# SoC_Supply.net
KiCad netlist of a schematic drawn in Altium Designer
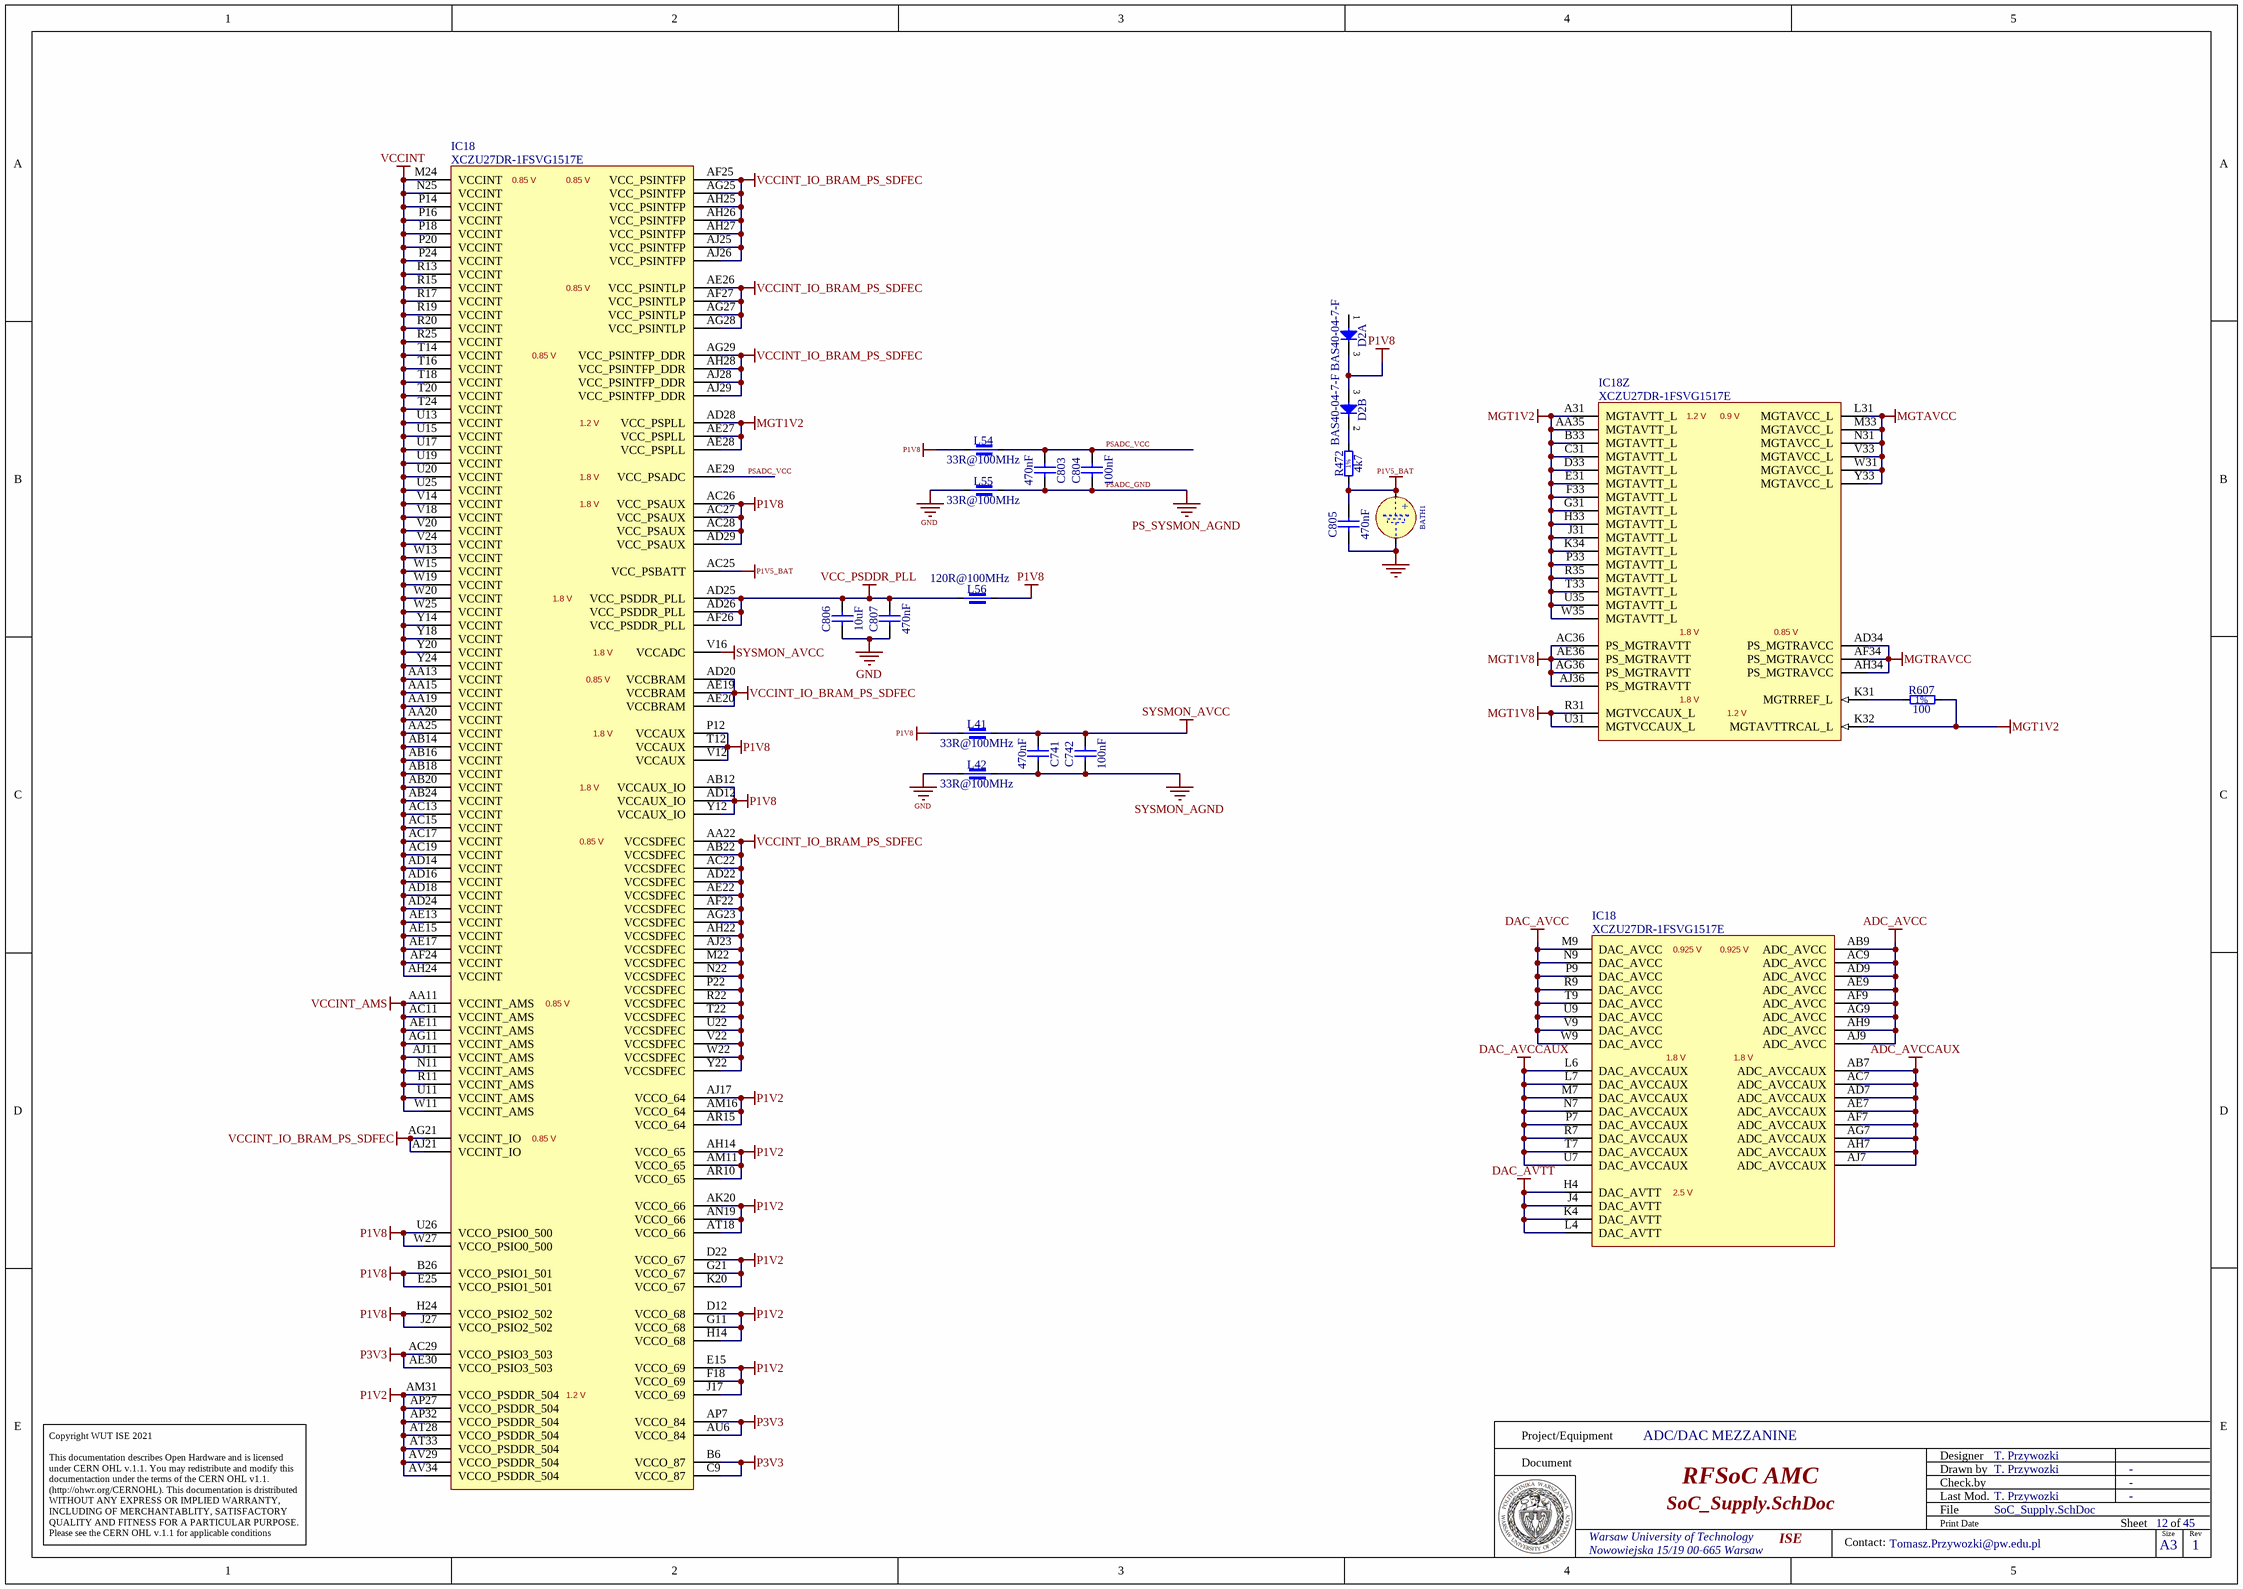
[diagram p0: SoC_Supply.SchDoc]

(export (version "E")
  (design (tool "Eeschema 10.0.6"))
  (components
    (comp (ref "BATH1")
      (value "~")
      (footprint "BATH_KEYSTONE_2998")
      (description "Battery Holder whit 2 Pin")
      (fields
        (field (name "PART NUMBER") "BATH_KEYSTONE_2998")
        (field (name "MANUFACTURER") "KEYSTONE")
        (field (name "AUTHOR") "CERN DEM JLC")
      )
      (libsource (lib "Eletro-mechanical") (part "Battery Holder 2 Pin"))
    )
    (comp (ref "C741")
      (value "470nF")
      (footprint "CAPC0603X33N")
      (description "Non-polarised capacitor")
      (fields
        (field (name "MANUFACTURER PART NUMBER") "CC0201_470NF_4V_20%_X5R")
        (field (name "MANUFACTURER") "GENERIC")
        (field (name "AUTHOR") "CERN DEM JLC")
      )
      (libsource (lib "Capacitors") (part "Capacitor - non polarized"))
    )
    (comp (ref "C742")
      (value "100nF")
      (footprint "CAPC1005X55N")
      (description "Non-polarised capacitor")
      (fields
        (field (name "PART NUMBER") "CC0402_100NF_25V_10%_X7R_YUDEN_TMK105B7104KVHF")
        (field (name "VOLTAGE") "25V")
        (field (name "AUTHOR") "CERN DEM JLC")
      )
      (libsource (lib "Capacitors") (part "Capacitor - non polarized"))
    )
    (comp (ref "C803")
      (value "470nF")
      (footprint "CAPC0603X33N")
      (description "Non-polarised capacitor")
      (fields
        (field (name "MANUFACTURER PART NUMBER") "CC0201_470NF_4V_20%_X5R")
        (field (name "MANUFACTURER") "GENERIC")
        (field (name "AUTHOR") "CERN DEM JLC")
      )
      (libsource (lib "Capacitors") (part "Capacitor - non polarized"))
    )
    (comp (ref "C804")
      (value "100nF")
      (footprint "CAPC1005X55N")
      (description "Non-polarised capacitor")
      (fields
        (field (name "PART NUMBER") "CC0402_100NF_25V_10%_X7R_YUDEN_TMK105B7104KVHF")
        (field (name "VOLTAGE") "25V")
        (field (name "AUTHOR") "CERN DEM JLC")
      )
      (libsource (lib "Capacitors") (part "Capacitor - non polarized"))
    )
    (comp (ref "C805")
      (value "470nF")
      (footprint "CAPC0603X33N")
      (description "Non-polarised capacitor")
      (fields
        (field (name "MANUFACTURER PART NUMBER") "CC0201_470NF_4V_20%_X5R")
        (field (name "MANUFACTURER") "GENERIC")
        (field (name "AUTHOR") "CERN DEM JLC")
      )
      (libsource (lib "Capacitors") (part "Capacitor - non polarized"))
    )
    (comp (ref "C806")
      (value "10uF")
      (footprint "CAPC1608X80N")
      (description "Non-polarised capacitor")
      (fields
        (field (name "PART NUMBER") "CC0603_10UF_10V_10%_X5R")
        (field (name "VOLTAGE") "10V")
        (field (name "AUTHOR") "CERN DEM JLC")
      )
      (libsource (lib "Capacitors") (part "Capacitor - non polarized"))
    )
    (comp (ref "C807")
      (value "470nF")
      (footprint "CAPC1005X55N")
      (description "Non-polarised capacitor")
      (fields
        (field (name "PART NUMBER") "CC0402_470NF_16V_10%_X5R")
        (field (name "VOLTAGE") "16V")
        (field (name "AUTHOR") "CERN DEM JLC")
      )
      (libsource (lib "Capacitors") (part "Capacitor - non polarized"))
    )
    (comp (ref "D2")
      (value "BAS40-04-7-F")
      (footprint "SOT95P240X110-3N")
      (description "Serial Diode")
      (fields
        (field (name "VOLTAGE") "40V")
        (field (name "POWER") "200mA")
        (field (name "AUTHOR") "CERN DEM JLC")
      )
      (libsource (lib "ICs And Semiconductors") (part "Diode x2 A1C3_A3C2"))
    )
    (comp (ref "IC18")
      (value "XCZU27DR-1FSVG1517E")
      (footprint "XILINX_FSVG1517 (XCZU27DR)")
      (fields (field (name "MANUFACTURER") "XILINX") (field (name "AUTHOR") "CERN DEM MR"))
      (libsource (lib "ICs And Semiconductors") (part "XCZU27DR-1FSVG1517E"))
    )
    (comp (ref "L41")
      (value "33R@100MHz")
      (footprint "INDC1005X55N")
      (fields
        (field (name "MANUFACTURER PART NUMBER") "BLM15PX330SN1D")
        (field (name "MANUFACTURER") "MURATA")
        (field (name "PART NUMBER") "IND0402_MURATA_BLM15PX330SN1D")
        (field (name "AUTHOR") "CERN DEM JMW")
      )
      (libsource (lib "Inductors & Transformers") (part "Ferrite Bead"))
    )
    (comp (ref "L42")
      (value "33R@100MHz")
      (footprint "INDC1005X55N")
      (fields
        (field (name "MANUFACTURER PART NUMBER") "BLM15PX330SN1D")
        (field (name "MANUFACTURER") "MURATA")
        (field (name "PART NUMBER") "IND0402_MURATA_BLM15PX330SN1D")
        (field (name "AUTHOR") "CERN DEM JMW")
      )
      (libsource (lib "Inductors & Transformers") (part "Ferrite Bead"))
    )
    (comp (ref "L54")
      (value "33R@100MHz")
      (footprint "INDC1005X55N")
      (fields
        (field (name "MANUFACTURER PART NUMBER") "BLM15PX330SN1D")
        (field (name "MANUFACTURER") "MURATA")
        (field (name "PART NUMBER") "IND0402_MURATA_BLM15PX330SN1D")
        (field (name "AUTHOR") "CERN DEM JMW")
      )
      (libsource (lib "Inductors & Transformers") (part "Ferrite Bead"))
    )
    (comp (ref "L55")
      (value "33R@100MHz")
      (footprint "INDC1005X55N")
      (fields
        (field (name "MANUFACTURER PART NUMBER") "BLM15PX330SN1D")
        (field (name "MANUFACTURER") "MURATA")
        (field (name "PART NUMBER") "IND0402_MURATA_BLM15PX330SN1D")
        (field (name "AUTHOR") "CERN DEM JMW")
      )
      (libsource (lib "Inductors & Transformers") (part "Ferrite Bead"))
    )
    (comp (ref "L56")
      (value "120R@100MHz")
      (footprint "INDC1608X95N")
      (fields
        (field (name "MANUFACTURER PART NUMBER") "BLM18PG121SN1D")
        (field (name "MANUFACTURER") "MURATA")
        (field (name "PART NUMBER") "IND0603_MURATA_BLM18PG121SN1D")
        (field (name "AUTHOR") "CERN DEM BC")
      )
      (libsource (lib "") (part "Ferrite Bead_1"))
    )
    (comp (ref "R472")
      (value "4k7")
      (footprint "RESC1005X40N")
      (description "Resistor - 1%")
      (fields
        (field (name "PART NUMBER") "R0402_4K7_1%_0.0625W_100PPM")
        (field (name "POWER") "0.0625W")
        (field (name "AUTHOR") "CERN DEM JLC")
      )
      (libsource (lib "Resistors") (part "Resistor - 1%"))
    )
    (comp (ref "R607")
      (value "100")
      (footprint "RESC1005X40N")
      (description "Resistor - 1%")
      (fields
        (field (name "PART NUMBER") "R0402_100R_1%_0.1W_100PPM")
        (field (name "POWER") "0.1W")
        (field (name "AUTHOR") "CERN DEM JLC")
      )
      (libsource (lib "Resistors") (part "Resistor - 1%"))
    )
  )
  (nets
    (net (code "1") (name "/PSADC_VCC") (class "Default")
      (node (ref "C803") (pin "2") (pinfunction "2_2") (pintype "passive"))
      (node (ref "C804") (pin "2") (pinfunction "2_2") (pintype "passive"))
      (node (ref "IC18") (pin "AE29") (pinfunction "VCC_PSADC_AE29") (pintype "power_in"))
      (node (ref "L54") (pin "2") (pinfunction "2_2") (pintype "passive"))
    )
    (net (code "2") (name "ADC_AVCC") (class "Default")
      (node (ref "IC18") (pin "AB9") (pinfunction "ADC_AVCC_AB9") (pintype "power_in"))
      (node (ref "IC18") (pin "AC9") (pinfunction "ADC_AVCC_AC9") (pintype "power_in"))
      (node (ref "IC18") (pin "AD9") (pinfunction "ADC_AVCC_AD9") (pintype "power_in"))
      (node (ref "IC18") (pin "AE9") (pinfunction "ADC_AVCC_AE9") (pintype "power_in"))
      (node (ref "IC18") (pin "AF9") (pinfunction "ADC_AVCC_AF9") (pintype "power_in"))
      (node (ref "IC18") (pin "AG9") (pinfunction "ADC_AVCC_AG9") (pintype "power_in"))
      (node (ref "IC18") (pin "AH9") (pinfunction "ADC_AVCC_AH9") (pintype "power_in"))
      (node (ref "IC18") (pin "AJ9") (pinfunction "ADC_AVCC_AJ9") (pintype "power_in"))
    )
    (net (code "3") (name "ADC_AVCCAUX") (class "Default")
      (node (ref "IC18") (pin "AB7") (pinfunction "ADC_AVCCAUX_AB7") (pintype "power_in"))
      (node (ref "IC18") (pin "AC7") (pinfunction "ADC_AVCCAUX_AC7") (pintype "power_in"))
      (node (ref "IC18") (pin "AD7") (pinfunction "ADC_AVCCAUX_AD7") (pintype "power_in"))
      (node (ref "IC18") (pin "AE7") (pinfunction "ADC_AVCCAUX_AE7") (pintype "power_in"))
      (node (ref "IC18") (pin "AF7") (pinfunction "ADC_AVCCAUX_AF7") (pintype "power_in"))
      (node (ref "IC18") (pin "AG7") (pinfunction "ADC_AVCCAUX_AG7") (pintype "power_in"))
      (node (ref "IC18") (pin "AH7") (pinfunction "ADC_AVCCAUX_AH7") (pintype "power_in"))
      (node (ref "IC18") (pin "AJ7") (pinfunction "ADC_AVCCAUX_AJ7") (pintype "power_in"))
    )
    (net (code "4") (name "DAC_AVCC") (class "Default")
      (node (ref "IC18") (pin "M9") (pinfunction "DAC_AVCC_M9") (pintype "power_in"))
      (node (ref "IC18") (pin "N9") (pinfunction "DAC_AVCC_N9") (pintype "power_in"))
      (node (ref "IC18") (pin "P9") (pinfunction "DAC_AVCC_P9") (pintype "power_in"))
      (node (ref "IC18") (pin "R9") (pinfunction "DAC_AVCC_R9") (pintype "power_in"))
      (node (ref "IC18") (pin "T9") (pinfunction "DAC_AVCC_T9") (pintype "power_in"))
      (node (ref "IC18") (pin "U9") (pinfunction "DAC_AVCC_U9") (pintype "power_in"))
      (node (ref "IC18") (pin "V9") (pinfunction "DAC_AVCC_V9") (pintype "power_in"))
      (node (ref "IC18") (pin "W9") (pinfunction "DAC_AVCC_W9") (pintype "power_in"))
    )
    (net (code "5") (name "DAC_AVCCAUX") (class "Default")
      (node (ref "IC18") (pin "L6") (pinfunction "DAC_AVCCAUX_L6") (pintype "power_in"))
      (node (ref "IC18") (pin "L7") (pinfunction "DAC_AVCCAUX_L7") (pintype "power_in"))
      (node (ref "IC18") (pin "M7") (pinfunction "DAC_AVCCAUX_M7") (pintype "power_in"))
      (node (ref "IC18") (pin "N7") (pinfunction "DAC_AVCCAUX_N7") (pintype "power_in"))
      (node (ref "IC18") (pin "P7") (pinfunction "DAC_AVCCAUX_P7") (pintype "power_in"))
      (node (ref "IC18") (pin "R7") (pinfunction "DAC_AVCCAUX_R7") (pintype "power_in"))
      (node (ref "IC18") (pin "T7") (pinfunction "DAC_AVCCAUX_T7") (pintype "power_in"))
      (node (ref "IC18") (pin "U7") (pinfunction "DAC_AVCCAUX_U7") (pintype "power_in"))
    )
    (net (code "6") (name "DAC_AVTT") (class "Default")
      (node (ref "IC18") (pin "H4") (pinfunction "DAC_AVTT_H4") (pintype "power_in"))
      (node (ref "IC18") (pin "J4") (pinfunction "DAC_AVTT_J4") (pintype "power_in"))
      (node (ref "IC18") (pin "K4") (pinfunction "DAC_AVTT_K4") (pintype "power_in"))
      (node (ref "IC18") (pin "L4") (pinfunction "DAC_AVTT_L4") (pintype "power_in"))
    )
    (net (code "7") (name "GND") (class "Default")
      (node (ref "BATH1") (pin "2") (pinfunction "MINUS_2") (pintype "power_in"))
      (node (ref "C805") (pin "1") (pinfunction "1_1") (pintype "passive"))
      (node (ref "C806") (pin "1") (pinfunction "1_1") (pintype "passive"))
      (node (ref "C807") (pin "1") (pinfunction "1_1") (pintype "passive"))
      (node (ref "L42") (pin "1") (pinfunction "1_1") (pintype "passive"))
      (node (ref "L55") (pin "1") (pinfunction "1_1") (pintype "passive"))
    )
    (net (code "8") (name "MGT1V2") (class "Default")
      (node (ref "IC18") (pin "A31") (pinfunction "MGTAVTT_L_A31") (pintype "power_in"))
      (node (ref "IC18") (pin "AA35") (pinfunction "MGTAVTT_L_AA35") (pintype "power_in"))
      (node (ref "IC18") (pin "AD28") (pinfunction "VCC_PSPLL_AD28") (pintype "power_in"))
      (node (ref "IC18") (pin "AE27") (pinfunction "VCC_PSPLL_AE27") (pintype "power_in"))
      (node (ref "IC18") (pin "AE28") (pinfunction "VCC_PSPLL_AE28") (pintype "power_in"))
      (node (ref "IC18") (pin "B33") (pinfunction "MGTAVTT_L_B33") (pintype "power_in"))
      (node (ref "IC18") (pin "C31") (pinfunction "MGTAVTT_L_C31") (pintype "power_in"))
      (node (ref "IC18") (pin "D33") (pinfunction "MGTAVTT_L_D33") (pintype "power_in"))
      (node (ref "IC18") (pin "E31") (pinfunction "MGTAVTT_L_E31") (pintype "power_in"))
      (node (ref "IC18") (pin "F33") (pinfunction "MGTAVTT_L_F33") (pintype "power_in"))
      (node (ref "IC18") (pin "G31") (pinfunction "MGTAVTT_L_G31") (pintype "power_in"))
      (node (ref "IC18") (pin "H33") (pinfunction "MGTAVTT_L_H33") (pintype "power_in"))
      (node (ref "IC18") (pin "J31") (pinfunction "MGTAVTT_L_J31") (pintype "power_in"))
      (node (ref "IC18") (pin "K32") (pinfunction "MGTAVTTRCAL_L_K32") (pintype "input"))
      (node (ref "IC18") (pin "K34") (pinfunction "MGTAVTT_L_K34") (pintype "power_in"))
      (node (ref "IC18") (pin "P33") (pinfunction "MGTAVTT_L_P33") (pintype "power_in"))
      (node (ref "IC18") (pin "R35") (pinfunction "MGTAVTT_L_R35") (pintype "power_in"))
      (node (ref "IC18") (pin "T33") (pinfunction "MGTAVTT_L_T33") (pintype "power_in"))
      (node (ref "IC18") (pin "U35") (pinfunction "MGTAVTT_L_U35") (pintype "power_in"))
      (node (ref "IC18") (pin "W35") (pinfunction "MGTAVTT_L_W35") (pintype "power_in"))
      (node (ref "R607") (pin "2") (pinfunction "2_2") (pintype "passive"))
    )
    (net (code "9") (name "MGT1V8") (class "Default")
      (node (ref "IC18") (pin "AC36") (pinfunction "PS_MGTRAVTT_AC36") (pintype "power_in"))
      (node (ref "IC18") (pin "AE36") (pinfunction "PS_MGTRAVTT_AE36") (pintype "power_in"))
      (node (ref "IC18") (pin "AG36") (pinfunction "PS_MGTRAVTT_AG36") (pintype "power_in"))
      (node (ref "IC18") (pin "AJ36") (pinfunction "PS_MGTRAVTT_AJ36") (pintype "power_in"))
      (node (ref "IC18") (pin "R31") (pinfunction "MGTVCCAUX_L_R31") (pintype "power_in"))
      (node (ref "IC18") (pin "U31") (pinfunction "MGTVCCAUX_L_U31") (pintype "power_in"))
    )
    (net (code "10") (name "MGTAVCC") (class "Default")
      (node (ref "IC18") (pin "L31") (pinfunction "MGTAVCC_L_L31") (pintype "power_in"))
      (node (ref "IC18") (pin "M33") (pinfunction "MGTAVCC_L_M33") (pintype "power_in"))
      (node (ref "IC18") (pin "N31") (pinfunction "MGTAVCC_L_N31") (pintype "power_in"))
      (node (ref "IC18") (pin "V33") (pinfunction "MGTAVCC_L_V33") (pintype "power_in"))
      (node (ref "IC18") (pin "W31") (pinfunction "MGTAVCC_L_W31") (pintype "power_in"))
      (node (ref "IC18") (pin "Y33") (pinfunction "MGTAVCC_L_Y33") (pintype "power_in"))
    )
    (net (code "11") (name "MGTRAVCC") (class "Default")
      (node (ref "IC18") (pin "AD34") (pinfunction "PS_MGTRAVCC_AD34") (pintype "power_in"))
      (node (ref "IC18") (pin "AF34") (pinfunction "PS_MGTRAVCC_AF34") (pintype "power_in"))
      (node (ref "IC18") (pin "AH34") (pinfunction "PS_MGTRAVCC_AH34") (pintype "power_in"))
    )
    (net (code "12") (name "Net-(D2B-C)") (class "Default")
      (node (ref "D2") (pin "2") (pinfunction "C_2") (pintype "passive"))
      (node (ref "R472") (pin "2") (pinfunction "2_2") (pintype "passive"))
    )
    (net (code "13") (name "Net-(IC18Z-MGTRREF_L)") (class "Default")
      (node (ref "IC18") (pin "K31") (pinfunction "MGTRREF_L_K31") (pintype "input"))
      (node (ref "R607") (pin "1") (pinfunction "1_1") (pintype "passive"))
    )
    (net (code "14") (name "P1V2") (class "Default")
      (node (ref "IC18") (pin "AH14") (pinfunction "VCCO_65_AH14") (pintype "power_in"))
      (node (ref "IC18") (pin "AJ17") (pinfunction "VCCO_64_AJ17") (pintype "power_in"))
      (node (ref "IC18") (pin "AK20") (pinfunction "VCCO_66_AK20") (pintype "power_in"))
      (node (ref "IC18") (pin "AM11") (pinfunction "VCCO_65_AM11") (pintype "power_in"))
      (node (ref "IC18") (pin "AM16") (pinfunction "VCCO_64_AM16") (pintype "power_in"))
      (node (ref "IC18") (pin "AM31") (pinfunction "VCCO_PSDDR_504_AM31") (pintype "power_in"))
      (node (ref "IC18") (pin "AN19") (pinfunction "VCCO_66_AN19") (pintype "power_in"))
      (node (ref "IC18") (pin "AP27") (pinfunction "VCCO_PSDDR_504_AP27") (pintype "power_in"))
      (node (ref "IC18") (pin "AP32") (pinfunction "VCCO_PSDDR_504_AP32") (pintype "power_in"))
      (node (ref "IC18") (pin "AR10") (pinfunction "VCCO_65_AR10") (pintype "power_in"))
      (node (ref "IC18") (pin "AR15") (pinfunction "VCCO_64_AR15") (pintype "power_in"))
      (node (ref "IC18") (pin "AT18") (pinfunction "VCCO_66_AT18") (pintype "power_in"))
      (node (ref "IC18") (pin "AT28") (pinfunction "VCCO_PSDDR_504_AT28") (pintype "power_in"))
      (node (ref "IC18") (pin "AT33") (pinfunction "VCCO_PSDDR_504_AT33") (pintype "power_in"))
      (node (ref "IC18") (pin "AV29") (pinfunction "VCCO_PSDDR_504_AV29") (pintype "power_in"))
      (node (ref "IC18") (pin "AV34") (pinfunction "VCCO_PSDDR_504_AV34") (pintype "power_in"))
      (node (ref "IC18") (pin "D12") (pinfunction "VCCO_68_D12") (pintype "power_in"))
      (node (ref "IC18") (pin "D22") (pinfunction "VCCO_67_D22") (pintype "power_in"))
      (node (ref "IC18") (pin "E15") (pinfunction "VCCO_69_E15") (pintype "power_in"))
      (node (ref "IC18") (pin "F18") (pinfunction "VCCO_69_F18") (pintype "power_in"))
      (node (ref "IC18") (pin "G11") (pinfunction "VCCO_68_G11") (pintype "power_in"))
      (node (ref "IC18") (pin "G21") (pinfunction "VCCO_67_G21") (pintype "power_in"))
      (node (ref "IC18") (pin "H14") (pinfunction "VCCO_68_H14") (pintype "power_in"))
      (node (ref "IC18") (pin "J17") (pinfunction "VCCO_69_J17") (pintype "power_in"))
      (node (ref "IC18") (pin "K20") (pinfunction "VCCO_67_K20") (pintype "power_in"))
    )
    (net (code "15") (name "P1V5_BAT") (class "Default")
      (node (ref "BATH1") (pin "1") (pinfunction "PLUS_1") (pintype "power_in"))
      (node (ref "C805") (pin "2") (pinfunction "2_2") (pintype "passive"))
      (node (ref "IC18") (pin "AC25") (pinfunction "VCC_PSBATT_AC25") (pintype "power_in"))
      (node (ref "R472") (pin "1") (pinfunction "1_1") (pintype "passive"))
    )
    (net (code "16") (name "P1V8") (class "Default")
      (node (ref "D2") (pin "3") (pinfunction "COMAC_3") (pintype "passive"))
      (node (ref "IC18") (pin "AB12") (pinfunction "VCCAUX_IO_AB12") (pintype "power_in"))
      (node (ref "IC18") (pin "AC26") (pinfunction "VCC_PSAUX_AC26") (pintype "power_in"))
      (node (ref "IC18") (pin "AC27") (pinfunction "VCC_PSAUX_AC27") (pintype "power_in"))
      (node (ref "IC18") (pin "AC28") (pinfunction "VCC_PSAUX_AC28") (pintype "power_in"))
      (node (ref "IC18") (pin "AD12") (pinfunction "VCCAUX_IO_AD12") (pintype "power_in"))
      (node (ref "IC18") (pin "AD29") (pinfunction "VCC_PSAUX_AD29") (pintype "power_in"))
      (node (ref "IC18") (pin "B26") (pinfunction "VCCO_PSIO1_501_B26") (pintype "power_in"))
      (node (ref "IC18") (pin "E25") (pinfunction "VCCO_PSIO1_501_E25") (pintype "power_in"))
      (node (ref "IC18") (pin "H24") (pinfunction "VCCO_PSIO2_502_H24") (pintype "power_in"))
      (node (ref "IC18") (pin "J27") (pinfunction "VCCO_PSIO2_502_J27") (pintype "power_in"))
      (node (ref "IC18") (pin "P12") (pinfunction "VCCAUX_P12") (pintype "power_in"))
      (node (ref "IC18") (pin "T12") (pinfunction "VCCAUX_T12") (pintype "power_in"))
      (node (ref "IC18") (pin "U26") (pinfunction "VCCO_PSIO0_500_U26") (pintype "power_in"))
      (node (ref "IC18") (pin "V12") (pinfunction "VCCAUX_V12") (pintype "power_in"))
      (node (ref "IC18") (pin "W27") (pinfunction "VCCO_PSIO0_500_W27") (pintype "power_in"))
      (node (ref "IC18") (pin "Y12") (pinfunction "VCCAUX_IO_Y12") (pintype "power_in"))
      (node (ref "L41") (pin "1") (pinfunction "1_1") (pintype "passive"))
      (node (ref "L54") (pin "1") (pinfunction "1_1") (pintype "passive"))
      (node (ref "L56") (pin "1") (pinfunction "1_1") (pintype "passive"))
    )
    (net (code "17") (name "P3V3") (class "Default")
      (node (ref "IC18") (pin "AC29") (pinfunction "VCCO_PSIO3_503_AC29") (pintype "power_in"))
      (node (ref "IC18") (pin "AE30") (pinfunction "VCCO_PSIO3_503_AE30") (pintype "power_in"))
      (node (ref "IC18") (pin "AP7") (pinfunction "VCCO_84_AP7") (pintype "power_in"))
      (node (ref "IC18") (pin "AU6") (pinfunction "VCCO_84_AU6") (pintype "power_in"))
      (node (ref "IC18") (pin "B6") (pinfunction "VCCO_87_B6") (pintype "power_in"))
      (node (ref "IC18") (pin "C9") (pinfunction "VCCO_87_C9") (pintype "power_in"))
    )
    (net (code "18") (name "PS_SYSMON_AGND") (class "Default")
      (node (ref "C803") (pin "1") (pinfunction "1_1") (pintype "passive"))
      (node (ref "C804") (pin "1") (pinfunction "1_1") (pintype "passive"))
      (node (ref "L55") (pin "2") (pinfunction "2_2") (pintype "passive"))
    )
    (net (code "19") (name "SYSMON_AGND") (class "Default")
      (node (ref "C741") (pin "1") (pinfunction "1_1") (pintype "passive"))
      (node (ref "C742") (pin "1") (pinfunction "1_1") (pintype "passive"))
      (node (ref "L42") (pin "2") (pinfunction "2_2") (pintype "passive"))
    )
    (net (code "20") (name "SYSMON_AVCC") (class "Default")
      (node (ref "C741") (pin "2") (pinfunction "2_2") (pintype "passive"))
      (node (ref "C742") (pin "2") (pinfunction "2_2") (pintype "passive"))
      (node (ref "IC18") (pin "V16") (pinfunction "VCCADC_V16") (pintype "power_in"))
      (node (ref "L41") (pin "2") (pinfunction "2_2") (pintype "passive"))
    )
    (net (code "21") (name "VCCINT") (class "Default")
      (node (ref "IC18") (pin "AA13") (pinfunction "VCCINT_AA13") (pintype "power_in"))
      (node (ref "IC18") (pin "AA15") (pinfunction "VCCINT_AA15") (pintype "power_in"))
      (node (ref "IC18") (pin "AA19") (pinfunction "VCCINT_AA19") (pintype "power_in"))
      (node (ref "IC18") (pin "AA20") (pinfunction "VCCINT_AA20") (pintype "power_in"))
      (node (ref "IC18") (pin "AA25") (pinfunction "VCCINT_AA25") (pintype "power_in"))
      (node (ref "IC18") (pin "AB14") (pinfunction "VCCINT_AB14") (pintype "power_in"))
      (node (ref "IC18") (pin "AB16") (pinfunction "VCCINT_AB16") (pintype "power_in"))
      (node (ref "IC18") (pin "AB18") (pinfunction "VCCINT_AB18") (pintype "power_in"))
      (node (ref "IC18") (pin "AB20") (pinfunction "VCCINT_AB20") (pintype "power_in"))
      (node (ref "IC18") (pin "AB24") (pinfunction "VCCINT_AB24") (pintype "power_in"))
      (node (ref "IC18") (pin "AC13") (pinfunction "VCCINT_AC13") (pintype "power_in"))
      (node (ref "IC18") (pin "AC15") (pinfunction "VCCINT_AC15") (pintype "power_in"))
      (node (ref "IC18") (pin "AC17") (pinfunction "VCCINT_AC17") (pintype "power_in"))
      (node (ref "IC18") (pin "AC19") (pinfunction "VCCINT_AC19") (pintype "power_in"))
      (node (ref "IC18") (pin "AD14") (pinfunction "VCCINT_AD14") (pintype "power_in"))
      (node (ref "IC18") (pin "AD16") (pinfunction "VCCINT_AD16") (pintype "power_in"))
      (node (ref "IC18") (pin "AD18") (pinfunction "VCCINT_AD18") (pintype "power_in"))
      (node (ref "IC18") (pin "AD24") (pinfunction "VCCINT_AD24") (pintype "power_in"))
      (node (ref "IC18") (pin "AE13") (pinfunction "VCCINT_AE13") (pintype "power_in"))
      (node (ref "IC18") (pin "AE15") (pinfunction "VCCINT_AE15") (pintype "power_in"))
      (node (ref "IC18") (pin "AE17") (pinfunction "VCCINT_AE17") (pintype "power_in"))
      (node (ref "IC18") (pin "AF24") (pinfunction "VCCINT_AF24") (pintype "power_in"))
      (node (ref "IC18") (pin "AH24") (pinfunction "VCCINT_AH24") (pintype "power_in"))
      (node (ref "IC18") (pin "M24") (pinfunction "VCCINT_M24") (pintype "power_in"))
      (node (ref "IC18") (pin "N25") (pinfunction "VCCINT_N25") (pintype "power_in"))
      (node (ref "IC18") (pin "P14") (pinfunction "VCCINT_P14") (pintype "power_in"))
      (node (ref "IC18") (pin "P16") (pinfunction "VCCINT_P16") (pintype "power_in"))
      (node (ref "IC18") (pin "P18") (pinfunction "VCCINT_P18") (pintype "power_in"))
      (node (ref "IC18") (pin "P20") (pinfunction "VCCINT_P20") (pintype "power_in"))
      (node (ref "IC18") (pin "P24") (pinfunction "VCCINT_P24") (pintype "power_in"))
      (node (ref "IC18") (pin "R13") (pinfunction "VCCINT_R13") (pintype "power_in"))
      (node (ref "IC18") (pin "R15") (pinfunction "VCCINT_R15") (pintype "power_in"))
      (node (ref "IC18") (pin "R17") (pinfunction "VCCINT_R17") (pintype "power_in"))
      (node (ref "IC18") (pin "R19") (pinfunction "VCCINT_R19") (pintype "power_in"))
      (node (ref "IC18") (pin "R20") (pinfunction "VCCINT_R20") (pintype "power_in"))
      (node (ref "IC18") (pin "R25") (pinfunction "VCCINT_R25") (pintype "power_in"))
      (node (ref "IC18") (pin "T14") (pinfunction "VCCINT_T14") (pintype "power_in"))
      (node (ref "IC18") (pin "T16") (pinfunction "VCCINT_T16") (pintype "power_in"))
      (node (ref "IC18") (pin "T18") (pinfunction "VCCINT_T18") (pintype "power_in"))
      (node (ref "IC18") (pin "T20") (pinfunction "VCCINT_T20") (pintype "power_in"))
      (node (ref "IC18") (pin "T24") (pinfunction "VCCINT_T24") (pintype "power_in"))
      (node (ref "IC18") (pin "U13") (pinfunction "VCCINT_U13") (pintype "power_in"))
      (node (ref "IC18") (pin "U15") (pinfunction "VCCINT_U15") (pintype "power_in"))
      (node (ref "IC18") (pin "U17") (pinfunction "VCCINT_U17") (pintype "power_in"))
      (node (ref "IC18") (pin "U19") (pinfunction "VCCINT_U19") (pintype "power_in"))
      (node (ref "IC18") (pin "U20") (pinfunction "VCCINT_U20") (pintype "power_in"))
      (node (ref "IC18") (pin "U25") (pinfunction "VCCINT_U25") (pintype "power_in"))
      (node (ref "IC18") (pin "V14") (pinfunction "VCCINT_V14") (pintype "power_in"))
      (node (ref "IC18") (pin "V18") (pinfunction "VCCINT_V18") (pintype "power_in"))
      (node (ref "IC18") (pin "V20") (pinfunction "VCCINT_V20") (pintype "power_in"))
      (node (ref "IC18") (pin "V24") (pinfunction "VCCINT_V24") (pintype "power_in"))
      (node (ref "IC18") (pin "W13") (pinfunction "VCCINT_W13") (pintype "power_in"))
      (node (ref "IC18") (pin "W15") (pinfunction "VCCINT_W15") (pintype "power_in"))
      (node (ref "IC18") (pin "W19") (pinfunction "VCCINT_W19") (pintype "power_in"))
      (node (ref "IC18") (pin "W20") (pinfunction "VCCINT_W20") (pintype "power_in"))
      (node (ref "IC18") (pin "W25") (pinfunction "VCCINT_W25") (pintype "power_in"))
      (node (ref "IC18") (pin "Y14") (pinfunction "VCCINT_Y14") (pintype "power_in"))
      (node (ref "IC18") (pin "Y18") (pinfunction "VCCINT_Y18") (pintype "power_in"))
      (node (ref "IC18") (pin "Y20") (pinfunction "VCCINT_Y20") (pintype "power_in"))
      (node (ref "IC18") (pin "Y24") (pinfunction "VCCINT_Y24") (pintype "power_in"))
    )
    (net (code "22") (name "VCCINT_AMS") (class "Default")
      (node (ref "IC18") (pin "AA11") (pinfunction "VCCINT_AMS_AA11") (pintype "power_in"))
      (node (ref "IC18") (pin "AC11") (pinfunction "VCCINT_AMS_AC11") (pintype "power_in"))
      (node (ref "IC18") (pin "AE11") (pinfunction "VCCINT_AMS_AE11") (pintype "power_in"))
      (node (ref "IC18") (pin "AG11") (pinfunction "VCCINT_AMS_AG11") (pintype "power_in"))
      (node (ref "IC18") (pin "AJ11") (pinfunction "VCCINT_AMS_AJ11") (pintype "power_in"))
      (node (ref "IC18") (pin "N11") (pinfunction "VCCINT_AMS_N11") (pintype "power_in"))
      (node (ref "IC18") (pin "R11") (pinfunction "VCCINT_AMS_R11") (pintype "power_in"))
      (node (ref "IC18") (pin "U11") (pinfunction "VCCINT_AMS_U11") (pintype "power_in"))
      (node (ref "IC18") (pin "W11") (pinfunction "VCCINT_AMS_W11") (pintype "power_in"))
    )
    (net (code "23") (name "VCCINT_IO_BRAM_PS_SDFEC") (class "Default")
      (node (ref "IC18") (pin "AA22") (pinfunction "VCCSDFEC_AA22") (pintype "power_in"))
      (node (ref "IC18") (pin "AB22") (pinfunction "VCCSDFEC_AB22") (pintype "power_in"))
      (node (ref "IC18") (pin "AC22") (pinfunction "VCCSDFEC_AC22") (pintype "power_in"))
      (node (ref "IC18") (pin "AD20") (pinfunction "VCCBRAM_AD20") (pintype "power_in"))
      (node (ref "IC18") (pin "AD22") (pinfunction "VCCSDFEC_AD22") (pintype "power_in"))
      (node (ref "IC18") (pin "AE19") (pinfunction "VCCBRAM_AE19") (pintype "power_in"))
      (node (ref "IC18") (pin "AE20") (pinfunction "VCCBRAM_AE20") (pintype "power_in"))
      (node (ref "IC18") (pin "AE22") (pinfunction "VCCSDFEC_AE22") (pintype "power_in"))
      (node (ref "IC18") (pin "AE26") (pinfunction "VCC_PSINTLP_AE26") (pintype "power_in"))
      (node (ref "IC18") (pin "AF22") (pinfunction "VCCSDFEC_AF22") (pintype "power_in"))
      (node (ref "IC18") (pin "AF25") (pinfunction "VCC_PSINTFP_AF25") (pintype "power_in"))
      (node (ref "IC18") (pin "AF27") (pinfunction "VCC_PSINTLP_AF27") (pintype "power_in"))
      (node (ref "IC18") (pin "AG21") (pinfunction "VCCINT_IO_AG21") (pintype "power_in"))
      (node (ref "IC18") (pin "AG23") (pinfunction "VCCSDFEC_AG23") (pintype "power_in"))
      (node (ref "IC18") (pin "AG25") (pinfunction "VCC_PSINTFP_AG25") (pintype "power_in"))
      (node (ref "IC18") (pin "AG27") (pinfunction "VCC_PSINTLP_AG27") (pintype "power_in"))
      (node (ref "IC18") (pin "AG28") (pinfunction "VCC_PSINTLP_AG28") (pintype "power_in"))
      (node (ref "IC18") (pin "AG29") (pinfunction "VCC_PSINTFP_DDR_AG29") (pintype "power_in"))
      (node (ref "IC18") (pin "AH22") (pinfunction "VCCSDFEC_AH22") (pintype "power_in"))
      (node (ref "IC18") (pin "AH25") (pinfunction "VCC_PSINTFP_AH25") (pintype "power_in"))
      (node (ref "IC18") (pin "AH26") (pinfunction "VCC_PSINTFP_AH26") (pintype "power_in"))
      (node (ref "IC18") (pin "AH27") (pinfunction "VCC_PSINTFP_AH27") (pintype "power_in"))
      (node (ref "IC18") (pin "AH28") (pinfunction "VCC_PSINTFP_DDR_AH28") (pintype "power_in"))
      (node (ref "IC18") (pin "AJ21") (pinfunction "VCCINT_IO_AJ21") (pintype "power_in"))
      (node (ref "IC18") (pin "AJ23") (pinfunction "VCCSDFEC_AJ23") (pintype "power_in"))
      (node (ref "IC18") (pin "AJ25") (pinfunction "VCC_PSINTFP_AJ25") (pintype "power_in"))
      (node (ref "IC18") (pin "AJ26") (pinfunction "VCC_PSINTFP_AJ26") (pintype "power_in"))
      (node (ref "IC18") (pin "AJ28") (pinfunction "VCC_PSINTFP_DDR_AJ28") (pintype "power_in"))
      (node (ref "IC18") (pin "AJ29") (pinfunction "VCC_PSINTFP_DDR_AJ29") (pintype "power_in"))
      (node (ref "IC18") (pin "M22") (pinfunction "VCCSDFEC_M22") (pintype "power_in"))
      (node (ref "IC18") (pin "N22") (pinfunction "VCCSDFEC_N22") (pintype "power_in"))
      (node (ref "IC18") (pin "P22") (pinfunction "VCCSDFEC_P22") (pintype "power_in"))
      (node (ref "IC18") (pin "R22") (pinfunction "VCCSDFEC_R22") (pintype "power_in"))
      (node (ref "IC18") (pin "T22") (pinfunction "VCCSDFEC_T22") (pintype "power_in"))
      (node (ref "IC18") (pin "U22") (pinfunction "VCCSDFEC_U22") (pintype "power_in"))
      (node (ref "IC18") (pin "V22") (pinfunction "VCCSDFEC_V22") (pintype "power_in"))
      (node (ref "IC18") (pin "W22") (pinfunction "VCCSDFEC_W22") (pintype "power_in"))
      (node (ref "IC18") (pin "Y22") (pinfunction "VCCSDFEC_Y22") (pintype "power_in"))
    )
    (net (code "24") (name "VCC_PSDDR_PLL") (class "Default")
      (node (ref "C806") (pin "2") (pinfunction "2_2") (pintype "passive"))
      (node (ref "C807") (pin "2") (pinfunction "2_2") (pintype "passive"))
      (node (ref "IC18") (pin "AD25") (pinfunction "VCC_PSDDR_PLL_AD25") (pintype "power_in"))
      (node (ref "IC18") (pin "AD26") (pinfunction "VCC_PSDDR_PLL_AD26") (pintype "power_in"))
      (node (ref "IC18") (pin "AF26") (pinfunction "VCC_PSDDR_PLL_AF26") (pintype "power_in"))
      (node (ref "L56") (pin "2") (pinfunction "2_2") (pintype "passive"))
    )
    (net (code "25") (name "unconnected-(D2A-A-Pad1)") (class "Default")
      (node (ref "D2") (pin "1") (pinfunction "A_1") (pintype "passive"))
    )
  )
)
